# ESP8266-12F.net
KiCad netlist of a schematic drawn in Altium Designer
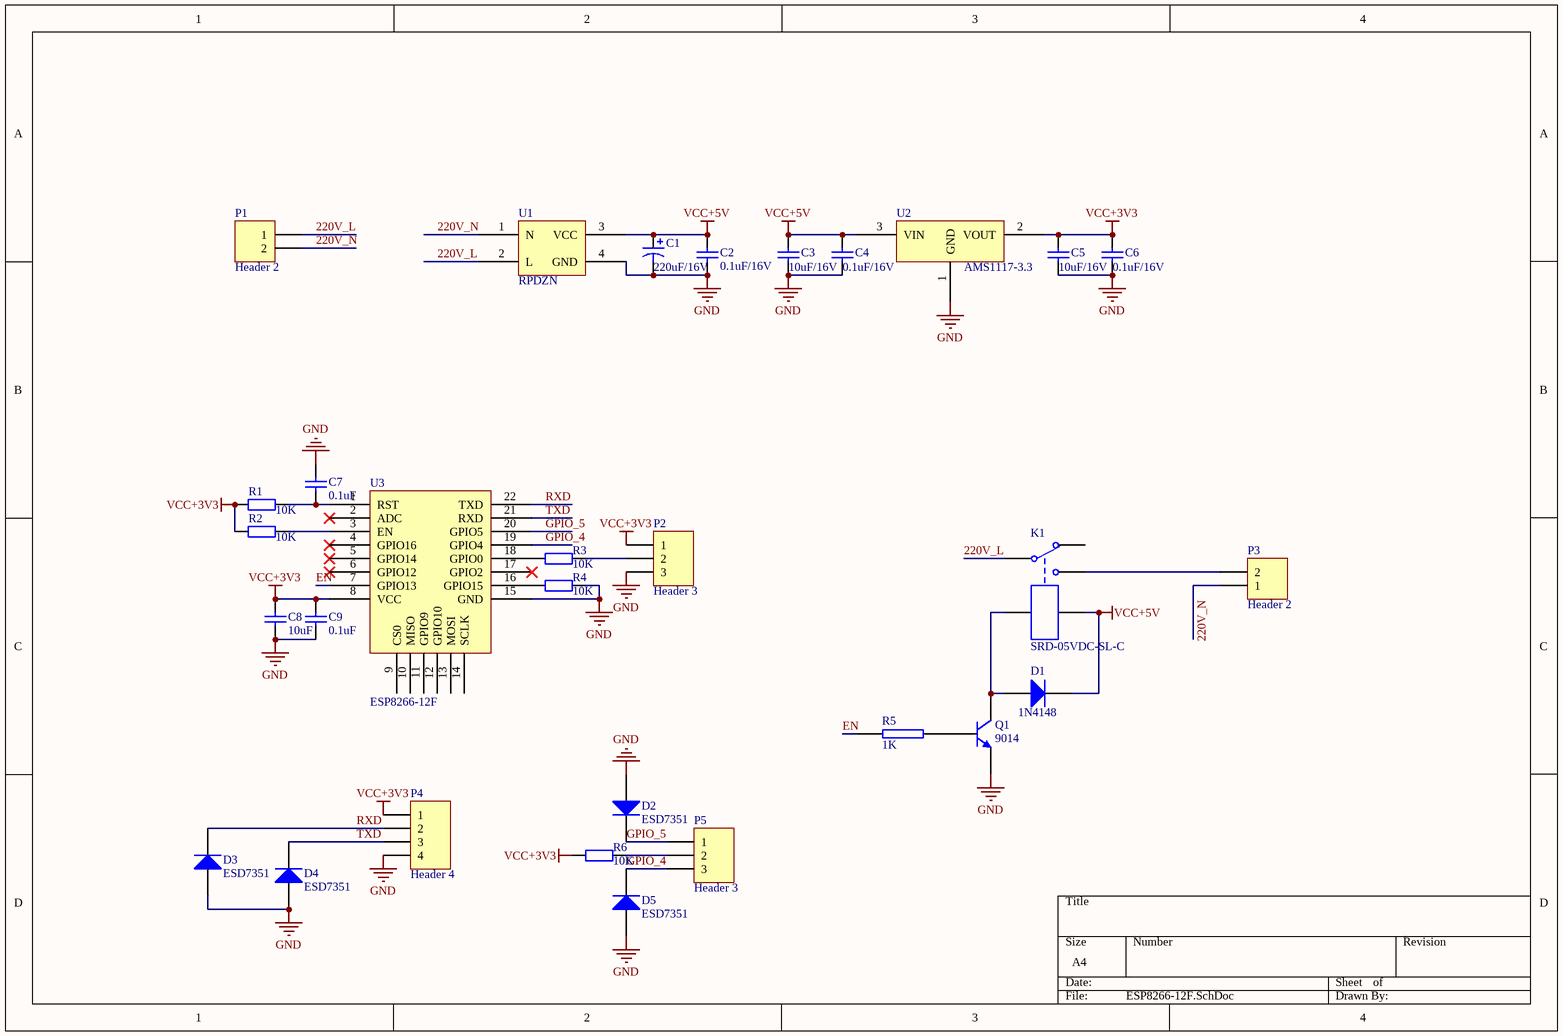
[diagram p0: ESP8266-12F.SchDoc]

(export (version "E")
  (design (tool "Eeschema 10.0.6"))
  (components
    (comp (ref "C1")
      (value "220uF/16V")
      (footprint "CAP6.3")
      (description "Polarized Capacitor (Radial)")
      (fields (field (name "PUBLISHER") "Altium Limited"))
      (libsource (lib "Miscellaneous Devices") (part "Cap Pol1"))
    )
    (comp (ref "C2")
      (value "0.1uF/16V")
      (footprint "0603C")
      (description "Capacitor")
      (fields (field (name "PUBLISHER") "Altium Limited"))
      (libsource (lib "Miscellaneous Devices") (part "Cap"))
    )
    (comp (ref "C3")
      (value "10uF/16V")
      (footprint "0603C")
      (description "Capacitor")
      (fields (field (name "PUBLISHER") "Altium Limited"))
      (libsource (lib "Miscellaneous Devices") (part "Cap"))
    )
    (comp (ref "C4")
      (value "0.1uF/16V")
      (footprint "0603C")
      (description "Capacitor")
      (fields (field (name "PUBLISHER") "Altium Limited"))
      (libsource (lib "Miscellaneous Devices") (part "Cap"))
    )
    (comp (ref "C5")
      (value "10uF/16V")
      (footprint "0603C")
      (description "Capacitor")
      (fields (field (name "PUBLISHER") "Altium Limited"))
      (libsource (lib "Miscellaneous Devices") (part "Cap"))
    )
    (comp (ref "C6")
      (value "0.1uF/16V")
      (footprint "0603C")
      (description "Capacitor")
      (fields (field (name "PUBLISHER") "Altium Limited"))
      (libsource (lib "Miscellaneous Devices") (part "Cap"))
    )
    (comp (ref "C7")
      (value "0.1uF")
      (footprint "0603C")
      (description "Capacitor")
      (fields (field (name "PUBLISHER") "Altium Limited"))
      (libsource (lib "Miscellaneous Devices") (part "Cap"))
    )
    (comp (ref "C8")
      (value "10uF")
      (footprint "0603C")
      (description "Capacitor")
      (fields (field (name "PUBLISHER") "Altium Limited"))
      (libsource (lib "Miscellaneous Devices") (part "Cap"))
    )
    (comp (ref "C9")
      (value "0.1uF")
      (footprint "0603C")
      (description "Capacitor")
      (fields (field (name "PUBLISHER") "Altium Limited"))
      (libsource (lib "Miscellaneous Devices") (part "Cap"))
    )
    (comp (ref "D1")
      (value "1N4148")
      (footprint "SOD-323")
      (description "1 Amp General Purpose Rectifier")
      (fields (field (name "PUBLISHER") "Altium Limited"))
      (libsource (lib "Miscellaneous Devices") (part "Diode 1N4001"))
    )
    (comp (ref "D2")
      (value "ESD7351")
      (footprint "SOD-323")
      (description "Default Diode")
      (fields (field (name "PUBLISHER") "Altium Limited"))
      (libsource (lib "Miscellaneous Devices") (part "Diode"))
    )
    (comp (ref "D3")
      (value "ESD7351")
      (footprint "SOD-323")
      (description "Default Diode")
      (fields (field (name "PUBLISHER") "Altium Limited"))
      (libsource (lib "Miscellaneous Devices") (part "Diode"))
    )
    (comp (ref "D4")
      (value "ESD7351")
      (footprint "SOD-323")
      (description "Default Diode")
      (fields (field (name "PUBLISHER") "Altium Limited"))
      (libsource (lib "Miscellaneous Devices") (part "Diode"))
    )
    (comp (ref "D5")
      (value "ESD7351")
      (footprint "SOD-323")
      (description "Default Diode")
      (fields (field (name "PUBLISHER") "Altium Limited"))
      (libsource (lib "Miscellaneous Devices") (part "Diode"))
    )
    (comp (ref "K1")
      (value "SRD-05VDC-SL-C")
      (footprint "SRD-05VDC-SL-C")
      (description "Single-Pole Dual-Throw Relay")
      (fields (field (name "PUBLISHER") "Altium Limited"))
      (libsource (lib "Miscellaneous Devices") (part "Relay-SPDT"))
    )
    (comp (ref "P1")
      (value "Header 2")
      (footprint "KF128-3.81-2P")
      (description "Header, 2-Pin")
      (fields (field (name "PUBLISHER") "Altium Limited"))
      (libsource (lib "") (part "Header 2_1"))
    )
    (comp (ref "P2")
      (value "Header 3")
      (footprint "HDR2.54-LI-3P")
      (description "Header, 3-Pin")
      (fields (field (name "PUBLISHER") "Altium Limited"))
      (libsource (lib "Miscellaneous Connectors") (part "Header 3"))
    )
    (comp (ref "P3")
      (value "Header 2")
      (footprint "KF128-3.81-2P")
      (description "Header, 2-Pin")
      (fields (field (name "PUBLISHER") "Altium Limited"))
      (libsource (lib "Miscellaneous Connectors") (part "Header 2"))
    )
    (comp (ref "P4")
      (value "Header 4")
      (footprint "HDR2.54-LI-4P")
      (description "Header, 4-Pin")
      (fields (field (name "PUBLISHER") "Altium Limited"))
      (libsource (lib "Miscellaneous Connectors") (part "Header 4"))
    )
    (comp (ref "P5")
      (value "Header 3")
      (footprint "KF128-3.81-3P")
      (description "Header, 3-Pin")
      (fields (field (name "PUBLISHER") "Altium Limited"))
      (libsource (lib "Miscellaneous Connectors") (part "Header 3"))
    )
    (comp (ref "Q1") (value "9014") (footprint "SOT23-3M") (libsource (lib "lifuting") (part "9014")))
    (comp (ref "R1")
      (value "10K")
      (footprint "0603R")
      (description "Resistor")
      (fields (field (name "PUBLISHER") "Altium Limited"))
      (libsource (lib "") (part "Res2_1"))
    )
    (comp (ref "R2")
      (value "10K")
      (footprint "0603R")
      (description "Resistor")
      (fields (field (name "PUBLISHER") "Altium Limited"))
      (libsource (lib "") (part "Res2_1"))
    )
    (comp (ref "R3")
      (value "10K")
      (footprint "0603R")
      (description "Resistor")
      (fields (field (name "PUBLISHER") "Altium Limited"))
      (libsource (lib "Miscellaneous Devices") (part "Res2"))
    )
    (comp (ref "R4")
      (value "10K")
      (footprint "0603R")
      (description "Resistor")
      (fields (field (name "PUBLISHER") "Altium Limited"))
      (libsource (lib "") (part "Res2_1"))
    )
    (comp (ref "R5") (value "1K") (footprint "0603R") (libsource (lib "*") (part "RES2")))
    (comp (ref "R6")
      (value "10K")
      (footprint "0603R")
      (description "Resistor")
      (fields (field (name "PUBLISHER") "Altium Limited"))
      (libsource (lib "Miscellaneous Devices") (part "Res2"))
    )
    (comp (ref "U1") (value "RPDZN") (footprint "RPDZN") (libsource (lib "ESP8266-12F") (part "RPDZN")))
    (comp (ref "U2")
      (value "AMS1117-3.3")
      (footprint "SOT223_M")
      (libsource (lib "ESP8266-12F") (part "AMS1117-3.3"))
    )
    (comp (ref "U3")
      (value "ESP8266-12F")
      (footprint "ESP-12E&F Module")
      (libsource (lib "ESP8266-12F") (part "ESP8266-12F"))
    )
  )
  (nets
    (net (code "1") (name "/220V_L") (class "Default")
      (node (ref "K1") (pin "1") (pinfunction "1_1") (pintype "passive"))
      (node (ref "P1") (pin "1") (pinfunction "1_1") (pintype "passive"))
      (node (ref "U1") (pin "2") (pinfunction "L_2") (pintype "passive"))
    )
    (net (code "2") (name "/220V_N") (class "Default")
      (node (ref "P1") (pin "2") (pinfunction "2_2") (pintype "passive"))
      (node (ref "P3") (pin "1") (pinfunction "1_1") (pintype "passive"))
      (node (ref "U1") (pin "1") (pinfunction "N_1") (pintype "passive"))
    )
    (net (code "3") (name "/EN") (class "Default")
      (node (ref "R5") (pin "2") (pinfunction "2_2") (pintype "passive"))
      (node (ref "U3") (pin "7") (pinfunction "GPIO13_7") (pintype "passive"))
    )
    (net (code "4") (name "/GPIO_4") (class "Default")
      (node (ref "D5") (pin "2") (pinfunction "K_2") (pintype "passive"))
      (node (ref "P5") (pin "3") (pinfunction "3_3") (pintype "passive"))
      (node (ref "U3") (pin "19") (pinfunction "GPIO4_19") (pintype "passive"))
    )
    (net (code "5") (name "/GPIO_5") (class "Default")
      (node (ref "D2") (pin "2") (pinfunction "K_2") (pintype "passive"))
      (node (ref "P5") (pin "1") (pinfunction "1_1") (pintype "passive"))
      (node (ref "U3") (pin "20") (pinfunction "GPIO5_20") (pintype "passive"))
    )
    (net (code "6") (name "/RXD") (class "Default")
      (node (ref "D3") (pin "2") (pinfunction "K_2") (pintype "passive"))
      (node (ref "P4") (pin "2") (pinfunction "2_2") (pintype "passive"))
      (node (ref "U3") (pin "22") (pinfunction "TXD_22") (pintype "passive"))
    )
    (net (code "7") (name "/TXD") (class "Default")
      (node (ref "D4") (pin "2") (pinfunction "K_2") (pintype "passive"))
      (node (ref "P4") (pin "3") (pinfunction "3_3") (pintype "passive"))
      (node (ref "U3") (pin "21") (pinfunction "RXD_21") (pintype "passive"))
    )
    (net (code "8") (name "GND") (class "Default")
      (node (ref "C1") (pin "2") (pinfunction "2_2") (pintype "passive"))
      (node (ref "C2") (pin "1") (pinfunction "1_1") (pintype "passive"))
      (node (ref "C3") (pin "1") (pinfunction "1_1") (pintype "passive"))
      (node (ref "C4") (pin "1") (pinfunction "1_1") (pintype "passive"))
      (node (ref "C5") (pin "1") (pinfunction "1_1") (pintype "passive"))
      (node (ref "C6") (pin "1") (pinfunction "1_1") (pintype "passive"))
      (node (ref "C7") (pin "1") (pinfunction "1_1") (pintype "passive"))
      (node (ref "C8") (pin "2") (pinfunction "2_2") (pintype "passive"))
      (node (ref "C9") (pin "2") (pinfunction "2_2") (pintype "passive"))
      (node (ref "D2") (pin "1") (pinfunction "A_1") (pintype "passive"))
      (node (ref "D3") (pin "1") (pinfunction "A_1") (pintype "passive"))
      (node (ref "D4") (pin "1") (pinfunction "A_1") (pintype "passive"))
      (node (ref "D5") (pin "1") (pinfunction "A_1") (pintype "passive"))
      (node (ref "P2") (pin "3") (pinfunction "3_3") (pintype "passive"))
      (node (ref "P4") (pin "4") (pinfunction "4_4") (pintype "passive"))
      (node (ref "Q1") (pin "2") (pinfunction "E_2") (pintype "passive"))
      (node (ref "R4") (pin "2") (pinfunction "2_2") (pintype "passive"))
      (node (ref "U1") (pin "4") (pinfunction "GND_4") (pintype "passive"))
      (node (ref "U2") (pin "1") (pinfunction "GND_1") (pintype "passive"))
      (node (ref "U3") (pin "15") (pinfunction "GND_15") (pintype "passive"))
    )
    (net (code "9") (name "Net-(D1-A)") (class "Default")
      (node (ref "D1") (pin "1") (pinfunction "A_1") (pintype "passive"))
      (node (ref "K1") (pin "4") (pinfunction "4_4") (pintype "passive"))
      (node (ref "Q1") (pin "3") (pinfunction "C_3") (pintype "passive"))
    )
    (net (code "10") (name "Net-(K1-Pad3)") (class "Default")
      (node (ref "K1") (pin "3") (pinfunction "3_3") (pintype "passive"))
      (node (ref "P3") (pin "2") (pinfunction "2_2") (pintype "passive"))
    )
    (net (code "11") (name "Net-(P2-Pad2)") (class "Default")
      (node (ref "P2") (pin "2") (pinfunction "2_2") (pintype "passive"))
      (node (ref "R3") (pin "1") (pinfunction "1_1") (pintype "passive"))
    )
    (net (code "12") (name "Net-(P5-Pad2)") (class "Default")
      (node (ref "P5") (pin "2") (pinfunction "2_2") (pintype "passive"))
      (node (ref "R6") (pin "1") (pinfunction "1_1") (pintype "passive"))
    )
    (net (code "13") (name "Net-(Q1-B)") (class "Default")
      (node (ref "Q1") (pin "1") (pinfunction "B_1") (pintype "passive"))
      (node (ref "R5") (pin "1") (pinfunction "1_1") (pintype "passive"))
    )
    (net (code "14") (name "Net-(U3-EN)") (class "Default")
      (node (ref "R2") (pin "2") (pinfunction "2_2") (pintype "passive"))
      (node (ref "U3") (pin "3") (pinfunction "EN_3") (pintype "passive"))
    )
    (net (code "15") (name "Net-(U3-GPIO0)") (class "Default")
      (node (ref "R3") (pin "2") (pinfunction "2_2") (pintype "passive"))
      (node (ref "U3") (pin "18") (pinfunction "GPIO0_18") (pintype "passive"))
    )
    (net (code "16") (name "Net-(U3-GPIO15)") (class "Default")
      (node (ref "R4") (pin "1") (pinfunction "1_1") (pintype "passive"))
      (node (ref "U3") (pin "16") (pinfunction "GPIO15_16") (pintype "passive"))
    )
    (net (code "17") (name "Net-(U3-RST)") (class "Default")
      (node (ref "C7") (pin "2") (pinfunction "2_2") (pintype "passive"))
      (node (ref "R1") (pin "2") (pinfunction "2_2") (pintype "passive"))
      (node (ref "U3") (pin "1") (pinfunction "RST_1") (pintype "passive"))
    )
    (net (code "18") (name "VCC+3V3") (class "Default")
      (node (ref "C5") (pin "2") (pinfunction "2_2") (pintype "passive"))
      (node (ref "C6") (pin "2") (pinfunction "2_2") (pintype "passive"))
      (node (ref "C8") (pin "1") (pinfunction "1_1") (pintype "passive"))
      (node (ref "C9") (pin "1") (pinfunction "1_1") (pintype "passive"))
      (node (ref "P2") (pin "1") (pinfunction "1_1") (pintype "passive"))
      (node (ref "P4") (pin "1") (pinfunction "1_1") (pintype "passive"))
      (node (ref "R1") (pin "1") (pinfunction "1_1") (pintype "passive"))
      (node (ref "R2") (pin "1") (pinfunction "1_1") (pintype "passive"))
      (node (ref "R6") (pin "2") (pinfunction "2_2") (pintype "passive"))
      (node (ref "U2") (pin "2") (pinfunction "VOUT_2") (pintype "passive"))
      (node (ref "U3") (pin "8") (pinfunction "VCC_8") (pintype "passive"))
    )
    (net (code "19") (name "VCC+5V") (class "Default")
      (node (ref "C1") (pin "1") (pinfunction "1_1") (pintype "passive"))
      (node (ref "C2") (pin "2") (pinfunction "2_2") (pintype "passive"))
      (node (ref "C3") (pin "2") (pinfunction "2_2") (pintype "passive"))
      (node (ref "C4") (pin "2") (pinfunction "2_2") (pintype "passive"))
      (node (ref "D1") (pin "2") (pinfunction "K_2") (pintype "passive"))
      (node (ref "K1") (pin "5") (pinfunction "5_5") (pintype "passive"))
      (node (ref "U1") (pin "3") (pinfunction "VCC_3") (pintype "passive"))
      (node (ref "U2") (pin "3") (pinfunction "VIN_3") (pintype "passive"))
    )
    (net (code "20") (name "unconnected-(K1-Pad2)") (class "Default")
      (node (ref "K1") (pin "2") (pinfunction "2_2") (pintype "passive"))
    )
    (net (code "21") (name "unconnected-(U3-ADC-Pad2)") (class "Default")
      (node (ref "U3") (pin "2") (pinfunction "ADC_2") (pintype "passive+no_connect"))
    )
    (net (code "22") (name "unconnected-(U3-CS0-Pad9)") (class "Default")
      (node (ref "U3") (pin "9") (pinfunction "CS0_9") (pintype "passive"))
    )
    (net (code "23") (name "unconnected-(U3-GPIO2-Pad17)") (class "Default")
      (node (ref "U3") (pin "17") (pinfunction "GPIO2_17") (pintype "passive+no_connect"))
    )
    (net (code "24") (name "unconnected-(U3-GPIO9-Pad11)") (class "Default")
      (node (ref "U3") (pin "11") (pinfunction "GPIO9_11") (pintype "passive"))
    )
    (net (code "25") (name "unconnected-(U3-GPIO10-Pad12)") (class "Default")
      (node (ref "U3") (pin "12") (pinfunction "GPIO10_12") (pintype "passive"))
    )
    (net (code "26") (name "unconnected-(U3-GPIO12-Pad6)") (class "Default")
      (node (ref "U3") (pin "6") (pinfunction "GPIO12_6") (pintype "passive+no_connect"))
    )
    (net (code "27") (name "unconnected-(U3-GPIO14-Pad5)") (class "Default")
      (node (ref "U3") (pin "5") (pinfunction "GPIO14_5") (pintype "passive+no_connect"))
    )
    (net (code "28") (name "unconnected-(U3-GPIO16-Pad4)") (class "Default")
      (node (ref "U3") (pin "4") (pinfunction "GPIO16_4") (pintype "passive+no_connect"))
    )
    (net (code "29") (name "unconnected-(U3-MISO-Pad10)") (class "Default")
      (node (ref "U3") (pin "10") (pinfunction "MISO_10") (pintype "passive"))
    )
    (net (code "30") (name "unconnected-(U3-MOSI-Pad13)") (class "Default")
      (node (ref "U3") (pin "13") (pinfunction "MOSI_13") (pintype "passive"))
    )
    (net (code "31") (name "unconnected-(U3-SCLK-Pad14)") (class "Default")
      (node (ref "U3") (pin "14") (pinfunction "SCLK_14") (pintype "passive"))
    )
  )
)
